# AS3364_DG412_bus_mixer_v1_4-4-layer.net
KiCad netlist of a schematic drawn in EAGLE
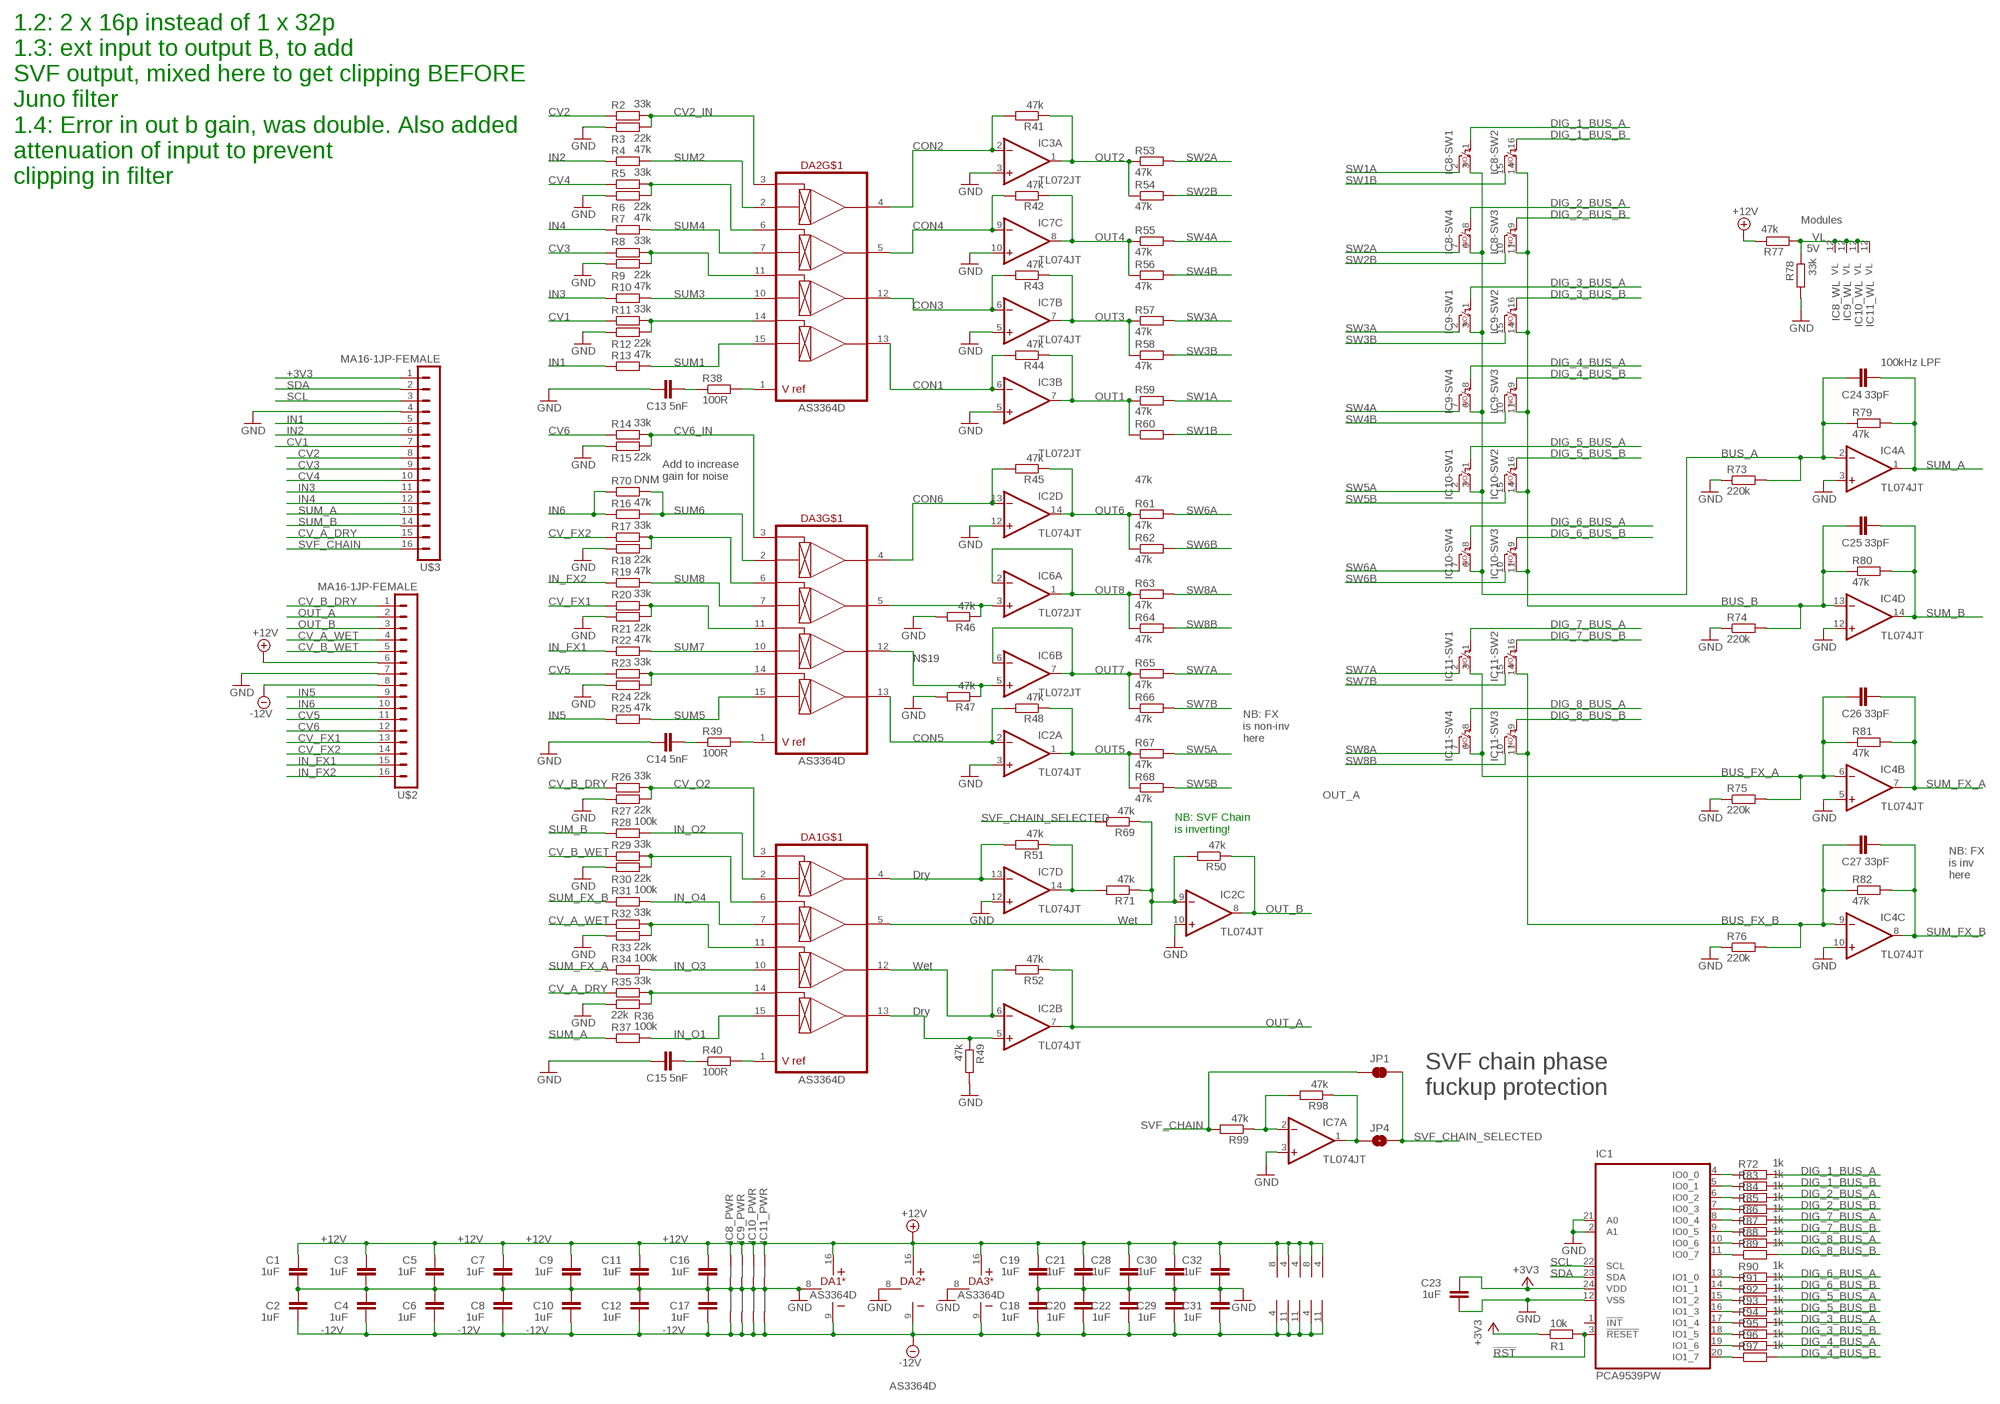
[diagram p0: schematic, sheet 1]

(export (version "E")
  (design (tool "Eeschema 10.0.6"))
  (components
    (comp (ref "C1")
      (value "1uF")
      (footprint "eagle-import:C0402-J")
      (libsource (lib "eagle-import") (part "C-EU-J0402"))
    )
    (comp (ref "C2")
      (value "1uF")
      (footprint "eagle-import:C0402-J")
      (libsource (lib "eagle-import") (part "C-EU-J0402"))
    )
    (comp (ref "C3")
      (value "1uF")
      (footprint "eagle-import:C0402-J")
      (libsource (lib "eagle-import") (part "C-EU-J0402"))
    )
    (comp (ref "C4")
      (value "1uF")
      (footprint "eagle-import:C0402-J")
      (libsource (lib "eagle-import") (part "C-EU-J0402"))
    )
    (comp (ref "C5")
      (value "1uF")
      (footprint "eagle-import:C0402-J")
      (libsource (lib "eagle-import") (part "C-EU-J0402"))
    )
    (comp (ref "C6")
      (value "1uF")
      (footprint "eagle-import:C0402-J")
      (libsource (lib "eagle-import") (part "C-EU-J0402"))
    )
    (comp (ref "C7")
      (value "1uF")
      (footprint "eagle-import:C0402-J")
      (libsource (lib "eagle-import") (part "C-EU-J0402"))
    )
    (comp (ref "C8")
      (value "1uF")
      (footprint "eagle-import:C0402-J")
      (libsource (lib "eagle-import") (part "C-EU-J0402"))
    )
    (comp (ref "C9")
      (value "1uF")
      (footprint "eagle-import:C0402-J")
      (libsource (lib "eagle-import") (part "C-EU-J0402"))
    )
    (comp (ref "C10")
      (value "1uF")
      (footprint "eagle-import:C0402-J")
      (libsource (lib "eagle-import") (part "C-EU-J0402"))
    )
    (comp (ref "C11")
      (value "1uF")
      (footprint "eagle-import:C0402-J")
      (libsource (lib "eagle-import") (part "C-EU-J0402"))
    )
    (comp (ref "C12")
      (value "1uF")
      (footprint "eagle-import:C0402-J")
      (libsource (lib "eagle-import") (part "C-EU-J0402"))
    )
    (comp (ref "C13")
      (value "5nF")
      (footprint "eagle-import:C0402-J")
      (libsource (lib "eagle-import") (part "C-EU-J0402"))
    )
    (comp (ref "C14")
      (value "5nF")
      (footprint "eagle-import:C0402-J")
      (libsource (lib "eagle-import") (part "C-EU-J0402"))
    )
    (comp (ref "C15")
      (value "5nF")
      (footprint "eagle-import:C0402-J")
      (libsource (lib "eagle-import") (part "C-EU-J0402"))
    )
    (comp (ref "C16")
      (value "1uF")
      (footprint "eagle-import:C0402-J")
      (libsource (lib "eagle-import") (part "C-EU-J0402"))
    )
    (comp (ref "C17")
      (value "1uF")
      (footprint "eagle-import:C0402-J")
      (libsource (lib "eagle-import") (part "C-EU-J0402"))
    )
    (comp (ref "C18")
      (value "1uF")
      (footprint "eagle-import:C0402-J")
      (libsource (lib "eagle-import") (part "C-EU-J0402"))
    )
    (comp (ref "C19")
      (value "1uF")
      (footprint "eagle-import:C0402-J")
      (libsource (lib "eagle-import") (part "C-EU-J0402"))
    )
    (comp (ref "C20")
      (value "1uF")
      (footprint "eagle-import:C0402-J")
      (libsource (lib "eagle-import") (part "C-EU-J0402"))
    )
    (comp (ref "C21")
      (value "1uF")
      (footprint "eagle-import:C0402-J")
      (libsource (lib "eagle-import") (part "C-EU-J0402"))
    )
    (comp (ref "C22")
      (value "1uF")
      (footprint "eagle-import:C0402-J")
      (libsource (lib "eagle-import") (part "C-EU-J0402"))
    )
    (comp (ref "C23")
      (value "1uF")
      (footprint "eagle-import:C0402-J")
      (libsource (lib "eagle-import") (part "C-EU-J0402"))
    )
    (comp (ref "C24")
      (value "33pF")
      (footprint "eagle-import:C0402-J")
      (libsource (lib "eagle-import") (part "C-EU-J0402"))
    )
    (comp (ref "C25")
      (value "33pF")
      (footprint "eagle-import:C0402-J")
      (libsource (lib "eagle-import") (part "C-EU-J0402"))
    )
    (comp (ref "C26")
      (value "33pF")
      (footprint "eagle-import:C0402-J")
      (libsource (lib "eagle-import") (part "C-EU-J0402"))
    )
    (comp (ref "C27")
      (value "33pF")
      (footprint "eagle-import:C0402-J")
      (libsource (lib "eagle-import") (part "C-EU-J0402"))
    )
    (comp (ref "C28")
      (value "1uF")
      (footprint "eagle-import:C0402-J")
      (libsource (lib "eagle-import") (part "C-EU-J0402"))
    )
    (comp (ref "C29")
      (value "1uF")
      (footprint "eagle-import:C0402-J")
      (libsource (lib "eagle-import") (part "C-EU-J0402"))
    )
    (comp (ref "C30")
      (value "1uF")
      (footprint "eagle-import:C0402-J")
      (libsource (lib "eagle-import") (part "C-EU-J0402"))
    )
    (comp (ref "C31")
      (value "1uF")
      (footprint "eagle-import:C0402-J")
      (libsource (lib "eagle-import") (part "C-EU-J0402"))
    )
    (comp (ref "C32")
      (value "1uF")
      (footprint "eagle-import:C0402-J")
      (libsource (lib "eagle-import") (part "C-EU-J0402"))
    )
    (comp (ref "DA1")
      (value "AS3364D")
      (footprint "eagle-import:DIL16J")
      (libsource (lib "eagle-import") (part "AS3364D"))
    )
    (comp (ref "DA2")
      (value "AS3364D")
      (footprint "eagle-import:DIL16J")
      (libsource (lib "eagle-import") (part "AS3364D"))
    )
    (comp (ref "DA3")
      (value "AS3364D")
      (footprint "eagle-import:DIL16J")
      (libsource (lib "eagle-import") (part "AS3364D"))
    )
    (comp (ref "IC1")
      (value "PCA9539PW")
      (footprint "eagle-import:TSSOP24J")
      (libsource (lib "eagle-import") (part "PCA9539PW"))
    )
    (comp (ref "IC2")
      (value "TL074JT")
      (footprint "eagle-import:TSSOP14J")
      (libsource (lib "eagle-import") (part "TL074JT"))
    )
    (comp (ref "IC3")
      (value "TL072JT")
      (footprint "eagle-import:TSSOP8J")
      (libsource (lib "eagle-import") (part "TL072JT"))
    )
    (comp (ref "IC4")
      (value "TL074JT")
      (footprint "eagle-import:TSSOP14J")
      (libsource (lib "eagle-import") (part "TL074JT"))
    )
    (comp (ref "IC6")
      (value "TL072JT")
      (footprint "eagle-import:TSSOP8J")
      (libsource (lib "eagle-import") (part "TL072JT"))
    )
    (comp (ref "IC7")
      (value "TL074JT")
      (footprint "eagle-import:TSSOP14J")
      (libsource (lib "eagle-import") (part "TL074JT"))
    )
    (comp (ref "IC8")
      (value "DG412-J")
      (footprint "eagle-import:DIL16J")
      (libsource (lib "eagle-import") (part "DG412-J"))
    )
    (comp (ref "IC9")
      (value "DG412-J")
      (footprint "eagle-import:DIL16J")
      (libsource (lib "eagle-import") (part "DG412-J"))
    )
    (comp (ref "IC10")
      (value "DG412-J")
      (footprint "eagle-import:DIL16J")
      (libsource (lib "eagle-import") (part "DG412-J"))
    )
    (comp (ref "IC11")
      (value "DG412-J")
      (footprint "eagle-import:DIL16J")
      (libsource (lib "eagle-import") (part "DG412-J"))
    )
    (comp (ref "JP1")
      (value "JUMPER-SMT_2_NC_TRACE_SILK-DNM")
      (footprint "eagle-import:SMT-JUMPER_2_NC_TRACE_SILK")
      (libsource (lib "eagle-import") (part "JUMPER-SMT_2_NC_TRACE_SILK"))
    )
    (comp (ref "JP4")
      (value "JUMPER-SMT_2_NO_SILK-DNM")
      (footprint "eagle-import:SMT-JUMPER_2_NO_SILK")
      (libsource (lib "eagle-import") (part "JUMPER-SMT_2_NO_SILK"))
    )
    (comp (ref "R1")
      (value "10k")
      (footprint "eagle-import:R0402")
      (libsource (lib "eagle-import") (part "R-EU_R0402"))
    )
    (comp (ref "R2")
      (value "33k")
      (footprint "eagle-import:R0402")
      (libsource (lib "eagle-import") (part "R-EU_R0402"))
    )
    (comp (ref "R3")
      (value "22k")
      (footprint "eagle-import:R0402")
      (libsource (lib "eagle-import") (part "R-EU_R0402"))
    )
    (comp (ref "R4")
      (value "47k")
      (footprint "eagle-import:R0402")
      (libsource (lib "eagle-import") (part "R-EU_R0402"))
    )
    (comp (ref "R5")
      (value "33k")
      (footprint "eagle-import:R0402")
      (libsource (lib "eagle-import") (part "R-EU_R0402"))
    )
    (comp (ref "R6")
      (value "22k")
      (footprint "eagle-import:R0402")
      (libsource (lib "eagle-import") (part "R-EU_R0402"))
    )
    (comp (ref "R7")
      (value "47k")
      (footprint "eagle-import:R0402")
      (libsource (lib "eagle-import") (part "R-EU_R0402"))
    )
    (comp (ref "R8")
      (value "33k")
      (footprint "eagle-import:R0402")
      (libsource (lib "eagle-import") (part "R-EU_R0402"))
    )
    (comp (ref "R9")
      (value "22k")
      (footprint "eagle-import:R0402")
      (libsource (lib "eagle-import") (part "R-EU_R0402"))
    )
    (comp (ref "R10")
      (value "47k")
      (footprint "eagle-import:R0402")
      (libsource (lib "eagle-import") (part "R-EU_R0402"))
    )
    (comp (ref "R11")
      (value "33k")
      (footprint "eagle-import:R0402")
      (libsource (lib "eagle-import") (part "R-EU_R0402"))
    )
    (comp (ref "R12")
      (value "22k")
      (footprint "eagle-import:R0402")
      (libsource (lib "eagle-import") (part "R-EU_R0402"))
    )
    (comp (ref "R13")
      (value "47k")
      (footprint "eagle-import:R0402")
      (libsource (lib "eagle-import") (part "R-EU_R0402"))
    )
    (comp (ref "R14")
      (value "33k")
      (footprint "eagle-import:R0402")
      (libsource (lib "eagle-import") (part "R-EU_R0402"))
    )
    (comp (ref "R15")
      (value "22k")
      (footprint "eagle-import:R0402")
      (libsource (lib "eagle-import") (part "R-EU_R0402"))
    )
    (comp (ref "R16")
      (value "47k")
      (footprint "eagle-import:R0402")
      (libsource (lib "eagle-import") (part "R-EU_R0402"))
    )
    (comp (ref "R17")
      (value "33k")
      (footprint "eagle-import:R0402")
      (libsource (lib "eagle-import") (part "R-EU_R0402"))
    )
    (comp (ref "R18")
      (value "22k")
      (footprint "eagle-import:R0402")
      (libsource (lib "eagle-import") (part "R-EU_R0402"))
    )
    (comp (ref "R19")
      (value "47k")
      (footprint "eagle-import:R0402")
      (libsource (lib "eagle-import") (part "R-EU_R0402"))
    )
    (comp (ref "R20")
      (value "33k")
      (footprint "eagle-import:R0402")
      (libsource (lib "eagle-import") (part "R-EU_R0402"))
    )
    (comp (ref "R21")
      (value "22k")
      (footprint "eagle-import:R0402")
      (libsource (lib "eagle-import") (part "R-EU_R0402"))
    )
    (comp (ref "R22")
      (value "47k")
      (footprint "eagle-import:R0402")
      (libsource (lib "eagle-import") (part "R-EU_R0402"))
    )
    (comp (ref "R23")
      (value "33k")
      (footprint "eagle-import:R0402")
      (libsource (lib "eagle-import") (part "R-EU_R0402"))
    )
    (comp (ref "R24")
      (value "22k")
      (footprint "eagle-import:R0402")
      (libsource (lib "eagle-import") (part "R-EU_R0402"))
    )
    (comp (ref "R25")
      (value "47k")
      (footprint "eagle-import:R0402")
      (libsource (lib "eagle-import") (part "R-EU_R0402"))
    )
    (comp (ref "R26")
      (value "33k")
      (footprint "eagle-import:R0402")
      (libsource (lib "eagle-import") (part "R-EU_R0402"))
    )
    (comp (ref "R27")
      (value "22k")
      (footprint "eagle-import:R0402")
      (libsource (lib "eagle-import") (part "R-EU_R0402"))
    )
    (comp (ref "R28")
      (value "100k")
      (footprint "eagle-import:R0402")
      (libsource (lib "eagle-import") (part "R-EU_R0402"))
    )
    (comp (ref "R29")
      (value "33k")
      (footprint "eagle-import:R0402")
      (libsource (lib "eagle-import") (part "R-EU_R0402"))
    )
    (comp (ref "R30")
      (value "22k")
      (footprint "eagle-import:R0402")
      (libsource (lib "eagle-import") (part "R-EU_R0402"))
    )
    (comp (ref "R31")
      (value "100k")
      (footprint "eagle-import:R0402")
      (libsource (lib "eagle-import") (part "R-EU_R0402"))
    )
    (comp (ref "R32")
      (value "33k")
      (footprint "eagle-import:R0402")
      (libsource (lib "eagle-import") (part "R-EU_R0402"))
    )
    (comp (ref "R33")
      (value "22k")
      (footprint "eagle-import:R0402")
      (libsource (lib "eagle-import") (part "R-EU_R0402"))
    )
    (comp (ref "R34")
      (value "100k")
      (footprint "eagle-import:R0402")
      (libsource (lib "eagle-import") (part "R-EU_R0402"))
    )
    (comp (ref "R35")
      (value "33k")
      (footprint "eagle-import:R0402")
      (libsource (lib "eagle-import") (part "R-EU_R0402"))
    )
    (comp (ref "R36")
      (value "22k")
      (footprint "eagle-import:R0402")
      (libsource (lib "eagle-import") (part "R-EU_R0402"))
    )
    (comp (ref "R37")
      (value "100k")
      (footprint "eagle-import:R0402")
      (libsource (lib "eagle-import") (part "R-EU_R0402"))
    )
    (comp (ref "R38")
      (value "100R")
      (footprint "eagle-import:R0402")
      (libsource (lib "eagle-import") (part "R-EU_R0402"))
    )
    (comp (ref "R39")
      (value "100R")
      (footprint "eagle-import:R0402")
      (libsource (lib "eagle-import") (part "R-EU_R0402"))
    )
    (comp (ref "R40")
      (value "100R")
      (footprint "eagle-import:R0402")
      (libsource (lib "eagle-import") (part "R-EU_R0402"))
    )
    (comp (ref "R41")
      (value "47k")
      (footprint "eagle-import:R0402")
      (libsource (lib "eagle-import") (part "R-EU_R0402"))
    )
    (comp (ref "R42")
      (value "47k")
      (footprint "eagle-import:R0402")
      (libsource (lib "eagle-import") (part "R-EU_R0402"))
    )
    (comp (ref "R43")
      (value "47k")
      (footprint "eagle-import:R0402")
      (libsource (lib "eagle-import") (part "R-EU_R0402"))
    )
    (comp (ref "R44")
      (value "47k")
      (footprint "eagle-import:R0402")
      (libsource (lib "eagle-import") (part "R-EU_R0402"))
    )
    (comp (ref "R45")
      (value "47k")
      (footprint "eagle-import:R0402")
      (libsource (lib "eagle-import") (part "R-EU_R0402"))
    )
    (comp (ref "R46")
      (value "47k")
      (footprint "eagle-import:R0402")
      (libsource (lib "eagle-import") (part "R-EU_R0402"))
    )
    (comp (ref "R47")
      (value "47k")
      (footprint "eagle-import:R0402")
      (libsource (lib "eagle-import") (part "R-EU_R0402"))
    )
    (comp (ref "R48")
      (value "47k")
      (footprint "eagle-import:R0402")
      (libsource (lib "eagle-import") (part "R-EU_R0402"))
    )
    (comp (ref "R49")
      (value "47k")
      (footprint "eagle-import:R0402")
      (libsource (lib "eagle-import") (part "R-EU_R0402"))
    )
    (comp (ref "R50")
      (value "47k")
      (footprint "eagle-import:R0402")
      (libsource (lib "eagle-import") (part "R-EU_R0402"))
    )
    (comp (ref "R51")
      (value "47k")
      (footprint "eagle-import:R0402")
      (libsource (lib "eagle-import") (part "R-EU_R0402"))
    )
    (comp (ref "R52")
      (value "47k")
      (footprint "eagle-import:R0402")
      (libsource (lib "eagle-import") (part "R-EU_R0402"))
    )
    (comp (ref "R53")
      (value "47k")
      (footprint "eagle-import:R0402")
      (libsource (lib "eagle-import") (part "R-EU_R0402"))
    )
    (comp (ref "R54")
      (value "47k")
      (footprint "eagle-import:R0402")
      (libsource (lib "eagle-import") (part "R-EU_R0402"))
    )
    (comp (ref "R55")
      (value "47k")
      (footprint "eagle-import:R0402")
      (libsource (lib "eagle-import") (part "R-EU_R0402"))
    )
    (comp (ref "R56")
      (value "47k")
      (footprint "eagle-import:R0402")
      (libsource (lib "eagle-import") (part "R-EU_R0402"))
    )
    (comp (ref "R57")
      (value "47k")
      (footprint "eagle-import:R0402")
      (libsource (lib "eagle-import") (part "R-EU_R0402"))
    )
    (comp (ref "R58")
      (value "47k")
      (footprint "eagle-import:R0402")
      (libsource (lib "eagle-import") (part "R-EU_R0402"))
    )
    (comp (ref "R59")
      (value "47k")
      (footprint "eagle-import:R0402")
      (libsource (lib "eagle-import") (part "R-EU_R0402"))
    )
    (comp (ref "R60")
      (value "47k")
      (footprint "eagle-import:R0402")
      (libsource (lib "eagle-import") (part "R-EU_R0402"))
    )
    (comp (ref "R61")
      (value "47k")
      (footprint "eagle-import:R0402")
      (libsource (lib "eagle-import") (part "R-EU_R0402"))
    )
    (comp (ref "R62")
      (value "47k")
      (footprint "eagle-import:R0402")
      (libsource (lib "eagle-import") (part "R-EU_R0402"))
    )
    (comp (ref "R63")
      (value "47k")
      (footprint "eagle-import:R0402")
      (libsource (lib "eagle-import") (part "R-EU_R0402"))
    )
    (comp (ref "R64")
      (value "47k")
      (footprint "eagle-import:R0402")
      (libsource (lib "eagle-import") (part "R-EU_R0402"))
    )
    (comp (ref "R65")
      (value "47k")
      (footprint "eagle-import:R0402")
      (libsource (lib "eagle-import") (part "R-EU_R0402"))
    )
    (comp (ref "R66")
      (value "47k")
      (footprint "eagle-import:R0402")
      (libsource (lib "eagle-import") (part "R-EU_R0402"))
    )
    (comp (ref "R67")
      (value "47k")
      (footprint "eagle-import:R0402")
      (libsource (lib "eagle-import") (part "R-EU_R0402"))
    )
    (comp (ref "R68")
      (value "47k")
      (footprint "eagle-import:R0402")
      (libsource (lib "eagle-import") (part "R-EU_R0402"))
    )
    (comp (ref "R69")
      (value "47k")
      (footprint "eagle-import:R0402")
      (libsource (lib "eagle-import") (part "R-EU_R0402"))
    )
    (comp (ref "R70")
      (value "DNM")
      (footprint "eagle-import:R0805")
      (libsource (lib "eagle-import") (part "R-EU_R0805"))
    )
    (comp (ref "R71")
      (value "47k")
      (footprint "eagle-import:R0402")
      (libsource (lib "eagle-import") (part "R-EU_R0402"))
    )
    (comp (ref "R72")
      (value "1k")
      (footprint "eagle-import:R0402")
      (libsource (lib "eagle-import") (part "R-EU_R0402"))
    )
    (comp (ref "R73")
      (value "220k")
      (footprint "eagle-import:R0603")
      (libsource (lib "eagle-import") (part "R-EU_R0603"))
    )
    (comp (ref "R74")
      (value "220k")
      (footprint "eagle-import:R0603")
      (libsource (lib "eagle-import") (part "R-EU_R0603"))
    )
    (comp (ref "R75")
      (value "220k")
      (footprint "eagle-import:R0603")
      (libsource (lib "eagle-import") (part "R-EU_R0603"))
    )
    (comp (ref "R76")
      (value "220k")
      (footprint "eagle-import:R0603")
      (libsource (lib "eagle-import") (part "R-EU_R0603"))
    )
    (comp (ref "R77")
      (value "47k")
      (footprint "eagle-import:R0402")
      (libsource (lib "eagle-import") (part "R-EU_R0402"))
    )
    (comp (ref "R78")
      (value "33k")
      (footprint "eagle-import:R0402")
      (libsource (lib "eagle-import") (part "R-EU_R0402"))
    )
    (comp (ref "R79")
      (value "47k")
      (footprint "eagle-import:R0402")
      (libsource (lib "eagle-import") (part "R-EU_R0402"))
    )
    (comp (ref "R80")
      (value "47k")
      (footprint "eagle-import:R0402")
      (libsource (lib "eagle-import") (part "R-EU_R0402"))
    )
    (comp (ref "R81")
      (value "47k")
      (footprint "eagle-import:R0402")
      (libsource (lib "eagle-import") (part "R-EU_R0402"))
    )
    (comp (ref "R82")
      (value "47k")
      (footprint "eagle-import:R0402")
      (libsource (lib "eagle-import") (part "R-EU_R0402"))
    )
    (comp (ref "R83")
      (value "1k")
      (footprint "eagle-import:R0402")
      (libsource (lib "eagle-import") (part "R-EU_R0402"))
    )
    (comp (ref "R84")
      (value "1k")
      (footprint "eagle-import:R0402")
      (libsource (lib "eagle-import") (part "R-EU_R0402"))
    )
    (comp (ref "R85")
      (value "1k")
      (footprint "eagle-import:R0402")
      (libsource (lib "eagle-import") (part "R-EU_R0402"))
    )
    (comp (ref "R86")
      (value "1k")
      (footprint "eagle-import:R0402")
      (libsource (lib "eagle-import") (part "R-EU_R0402"))
    )
    (comp (ref "R87")
      (value "1k")
      (footprint "eagle-import:R0402")
      (libsource (lib "eagle-import") (part "R-EU_R0402"))
    )
    (comp (ref "R88")
      (value "1k")
      (footprint "eagle-import:R0402")
      (libsource (lib "eagle-import") (part "R-EU_R0402"))
    )
    (comp (ref "R89")
      (value "1k")
      (footprint "eagle-import:R0402")
      (libsource (lib "eagle-import") (part "R-EU_R0402"))
    )
    (comp (ref "R90")
      (value "1k")
      (footprint "eagle-import:R0402")
      (libsource (lib "eagle-import") (part "R-EU_R0402"))
    )
    (comp (ref "R91")
      (value "1k")
      (footprint "eagle-import:R0402")
      (libsource (lib "eagle-import") (part "R-EU_R0402"))
    )
    (comp (ref "R92")
      (value "1k")
      (footprint "eagle-import:R0402")
      (libsource (lib "eagle-import") (part "R-EU_R0402"))
    )
    (comp (ref "R93")
      (value "1k")
      (footprint "eagle-import:R0402")
      (libsource (lib "eagle-import") (part "R-EU_R0402"))
    )
    (comp (ref "R94")
      (value "1k")
      (footprint "eagle-import:R0402")
      (libsource (lib "eagle-import") (part "R-EU_R0402"))
    )
    (comp (ref "R95")
      (value "1k")
      (footprint "eagle-import:R0402")
      (libsource (lib "eagle-import") (part "R-EU_R0402"))
    )
    (comp (ref "R96")
      (value "1k")
      (footprint "eagle-import:R0402")
      (libsource (lib "eagle-import") (part "R-EU_R0402"))
    )
    (comp (ref "R97")
      (value "1k")
      (footprint "eagle-import:R0402")
      (libsource (lib "eagle-import") (part "R-EU_R0402"))
    )
    (comp (ref "R98")
      (value "47k")
      (footprint "eagle-import:R0402")
      (libsource (lib "eagle-import") (part "R-EU_R0402"))
    )
    (comp (ref "R99")
      (value "47k")
      (footprint "eagle-import:R0402")
      (libsource (lib "eagle-import") (part "R-EU_R0402"))
    )
    (comp (ref "U$2")
      (value "MA16-1JP-FEMALE")
      (footprint "eagle-import:SIP-PIN16-1J")
      (libsource (lib "eagle-import") (part "MA16-1JP"))
    )
    (comp (ref "U$3")
      (value "MA16-1JP-FEMALE")
      (footprint "eagle-import:SIP-PIN16-1J")
      (libsource (lib "eagle-import") (part "MA16-1JP"))
    )
  )
  (nets
    (net (code "1") (name "+3V3") (class "Default")
      (node (ref "C23") (pin "2") (pinfunction "2_2") (pintype "passive"))
      (node (ref "IC1") (pin "24") (pinfunction "VDD_24") (pintype "power_in"))
      (node (ref "R1") (pin "1") (pinfunction "1_1") (pintype "passive"))
      (node (ref "U$3") (pin "1") (pinfunction "1_1") (pintype "passive"))
    )
    (net (code "2") (name "+12V") (class "Default")
      (node (ref "C1") (pin "2") (pinfunction "2_2") (pintype "passive"))
      (node (ref "C11") (pin "2") (pinfunction "2_2") (pintype "passive"))
      (node (ref "C16") (pin "2") (pinfunction "2_2") (pintype "passive"))
      (node (ref "C19") (pin "2") (pinfunction "2_2") (pintype "passive"))
      (node (ref "C21") (pin "2") (pinfunction "2_2") (pintype "passive"))
      (node (ref "C28") (pin "2") (pinfunction "2_2") (pintype "passive"))
      (node (ref "C3") (pin "2") (pinfunction "2_2") (pintype "passive"))
      (node (ref "C30") (pin "2") (pinfunction "2_2") (pintype "passive"))
      (node (ref "C32") (pin "2") (pinfunction "2_2") (pintype "passive"))
      (node (ref "C5") (pin "2") (pinfunction "2_2") (pintype "passive"))
      (node (ref "C7") (pin "2") (pinfunction "2_2") (pintype "passive"))
      (node (ref "C9") (pin "2") (pinfunction "2_2") (pintype "passive"))
      (node (ref "DA1") (pin "16") (pinfunction "V+_16") (pintype "power_in"))
      (node (ref "DA2") (pin "16") (pinfunction "V+_16") (pintype "power_in"))
      (node (ref "DA3") (pin "16") (pinfunction "V+_16") (pintype "power_in"))
      (node (ref "IC10") (pin "13") (pinfunction "+15V_13") (pintype "power_in"))
      (node (ref "IC11") (pin "13") (pinfunction "+15V_13") (pintype "power_in"))
      (node (ref "IC2") (pin "4") (pinfunction "V+_4") (pintype "power_in"))
      (node (ref "IC3") (pin "8") (pinfunction "V+_8") (pintype "power_in"))
      (node (ref "IC4") (pin "4") (pinfunction "V+_4") (pintype "power_in"))
      (node (ref "IC6") (pin "8") (pinfunction "V+_8") (pintype "power_in"))
      (node (ref "IC7") (pin "4") (pinfunction "V+_4") (pintype "power_in"))
      (node (ref "IC8") (pin "13") (pinfunction "+15V_13") (pintype "power_in"))
      (node (ref "IC9") (pin "13") (pinfunction "+15V_13") (pintype "power_in"))
      (node (ref "R77") (pin "1") (pinfunction "1_1") (pintype "passive"))
      (node (ref "U$2") (pin "6") (pinfunction "6_6") (pintype "passive"))
    )
    (net (code "3") (name "-12V") (class "Default")
      (node (ref "C10") (pin "1") (pinfunction "1_1") (pintype "passive"))
      (node (ref "C12") (pin "1") (pinfunction "1_1") (pintype "passive"))
      (node (ref "C17") (pin "1") (pinfunction "1_1") (pintype "passive"))
      (node (ref "C18") (pin "1") (pinfunction "1_1") (pintype "passive"))
      (node (ref "C2") (pin "1") (pinfunction "1_1") (pintype "passive"))
      (node (ref "C20") (pin "1") (pinfunction "1_1") (pintype "passive"))
      (node (ref "C22") (pin "1") (pinfunction "1_1") (pintype "passive"))
      (node (ref "C29") (pin "1") (pinfunction "1_1") (pintype "passive"))
      (node (ref "C31") (pin "1") (pinfunction "1_1") (pintype "passive"))
      (node (ref "C4") (pin "1") (pinfunction "1_1") (pintype "passive"))
      (node (ref "C6") (pin "1") (pinfunction "1_1") (pintype "passive"))
      (node (ref "C8") (pin "1") (pinfunction "1_1") (pintype "passive"))
      (node (ref "DA1") (pin "9") (pinfunction "V-_9") (pintype "power_in"))
      (node (ref "DA2") (pin "9") (pinfunction "V-_9") (pintype "power_in"))
      (node (ref "DA3") (pin "9") (pinfunction "V-_9") (pintype "power_in"))
      (node (ref "IC10") (pin "4") (pinfunction "-15V_4") (pintype "power_in"))
      (node (ref "IC11") (pin "4") (pinfunction "-15V_4") (pintype "power_in"))
      (node (ref "IC2") (pin "11") (pinfunction "V-_11") (pintype "power_in"))
      (node (ref "IC3") (pin "4") (pinfunction "V-_4") (pintype "power_in"))
      (node (ref "IC4") (pin "11") (pinfunction "V-_11") (pintype "power_in"))
      (node (ref "IC6") (pin "4") (pinfunction "V-_4") (pintype "power_in"))
      (node (ref "IC7") (pin "11") (pinfunction "V-_11") (pintype "power_in"))
      (node (ref "IC8") (pin "4") (pinfunction "-15V_4") (pintype "power_in"))
      (node (ref "IC9") (pin "4") (pinfunction "-15V_4") (pintype "power_in"))
      (node (ref "U$2") (pin "8") (pinfunction "8_8") (pintype "passive"))
    )
    (net (code "4") (name "/BUS_A") (class "Default")
      (node (ref "C24") (pin "1") (pinfunction "1_1") (pintype "passive"))
      (node (ref "IC10") (pin "3") (pinfunction "S_3") (pintype "bidirectional"))
      (node (ref "IC10") (pin "6") (pinfunction "S_6") (pintype "bidirectional"))
      (node (ref "IC4") (pin "2") (pinfunction "-IN_2") (pintype "input"))
      (node (ref "IC8") (pin "3") (pinfunction "S_3") (pintype "bidirectional"))
      (node (ref "IC8") (pin "6") (pinfunction "S_6") (pintype "bidirectional"))
      (node (ref "IC9") (pin "3") (pinfunction "S_3") (pintype "bidirectional"))
      (node (ref "IC9") (pin "6") (pinfunction "S_6") (pintype "bidirectional"))
      (node (ref "R73") (pin "2") (pinfunction "2_2") (pintype "passive"))
      (node (ref "R79") (pin "1") (pinfunction "1_1") (pintype "passive"))
    )
    (net (code "5") (name "/BUS_B") (class "Default")
      (node (ref "C25") (pin "1") (pinfunction "1_1") (pintype "passive"))
      (node (ref "IC10") (pin "11") (pinfunction "S_11") (pintype "bidirectional"))
      (node (ref "IC10") (pin "14") (pinfunction "S_14") (pintype "bidirectional"))
      (node (ref "IC4") (pin "13") (pinfunction "-IN_13") (pintype "input"))
      (node (ref "IC8") (pin "11") (pinfunction "S_11") (pintype "bidirectional"))
      (node (ref "IC8") (pin "14") (pinfunction "S_14") (pintype "bidirectional"))
      (node (ref "IC9") (pin "11") (pinfunction "S_11") (pintype "bidirectional"))
      (node (ref "IC9") (pin "14") (pinfunction "S_14") (pintype "bidirectional"))
      (node (ref "R74") (pin "2") (pinfunction "2_2") (pintype "passive"))
      (node (ref "R80") (pin "1") (pinfunction "1_1") (pintype "passive"))
    )
    (net (code "6") (name "/BUS_FX_A") (class "Default")
      (node (ref "C26") (pin "1") (pinfunction "1_1") (pintype "passive"))
      (node (ref "IC11") (pin "3") (pinfunction "S_3") (pintype "bidirectional"))
      (node (ref "IC11") (pin "6") (pinfunction "S_6") (pintype "bidirectional"))
      (node (ref "IC4") (pin "6") (pinfunction "-IN_6") (pintype "input"))
      (node (ref "R75") (pin "2") (pinfunction "2_2") (pintype "passive"))
      (node (ref "R81") (pin "1") (pinfunction "1_1") (pintype "passive"))
    )
    (net (code "7") (name "/BUS_FX_B") (class "Default")
      (node (ref "C27") (pin "1") (pinfunction "1_1") (pintype "passive"))
      (node (ref "IC11") (pin "11") (pinfunction "S_11") (pintype "bidirectional"))
      (node (ref "IC11") (pin "14") (pinfunction "S_14") (pintype "bidirectional"))
      (node (ref "IC4") (pin "9") (pinfunction "-IN_9") (pintype "input"))
      (node (ref "R76") (pin "2") (pinfunction "2_2") (pintype "passive"))
      (node (ref "R82") (pin "1") (pinfunction "1_1") (pintype "passive"))
    )
    (net (code "8") (name "/CON1") (class "Default")
      (node (ref "DA2") (pin "13") (pinfunction "OUT4_13") (pintype "output"))
      (node (ref "IC3") (pin "6") (pinfunction "-IN_6") (pintype "input"))
      (node (ref "R44") (pin "2") (pinfunction "2_2") (pintype "passive"))
    )
    (net (code "9") (name "/CON2") (class "Default")
      (node (ref "DA2") (pin "4") (pinfunction "OUT1_4") (pintype "output"))
      (node (ref "IC3") (pin "2") (pinfunction "-IN_2") (pintype "input"))
      (node (ref "R41") (pin "2") (pinfunction "2_2") (pintype "passive"))
    )
    (net (code "10") (name "/CON3") (class "Default")
      (node (ref "DA2") (pin "12") (pinfunction "OUT3_12") (pintype "output"))
      (node (ref "IC7") (pin "6") (pinfunction "-IN_6") (pintype "input"))
      (node (ref "R43") (pin "2") (pinfunction "2_2") (pintype "passive"))
    )
    (net (code "11") (name "/CON4") (class "Default")
      (node (ref "DA2") (pin "5") (pinfunction "OUT2_5") (pintype "output"))
      (node (ref "IC7") (pin "9") (pinfunction "-IN_9") (pintype "input"))
      (node (ref "R42") (pin "2") (pinfunction "2_2") (pintype "passive"))
    )
    (net (code "12") (name "/CON5") (class "Default")
      (node (ref "DA3") (pin "13") (pinfunction "OUT4_13") (pintype "output"))
      (node (ref "IC2") (pin "2") (pinfunction "-IN_2") (pintype "input"))
      (node (ref "R48") (pin "2") (pinfunction "2_2") (pintype "passive"))
    )
    (net (code "13") (name "/CON6") (class "Default")
      (node (ref "DA3") (pin "4") (pinfunction "OUT1_4") (pintype "output"))
      (node (ref "IC2") (pin "13") (pinfunction "-IN_13") (pintype "input"))
      (node (ref "R45") (pin "2") (pinfunction "2_2") (pintype "passive"))
    )
    (net (code "14") (name "/CV1") (class "Default")
      (node (ref "R11") (pin "1") (pinfunction "1_1") (pintype "passive"))
      (node (ref "U$3") (pin "7") (pinfunction "7_7") (pintype "passive"))
    )
    (net (code "15") (name "/CV2") (class "Default")
      (node (ref "R2") (pin "1") (pinfunction "1_1") (pintype "passive"))
      (node (ref "U$3") (pin "8") (pinfunction "8_8") (pintype "passive"))
    )
    (net (code "16") (name "/CV2_IN") (class "Default")
      (node (ref "DA2") (pin "3") (pinfunction "CV1_3") (pintype "input"))
      (node (ref "R2") (pin "2") (pinfunction "2_2") (pintype "passive"))
      (node (ref "R3") (pin "2") (pinfunction "2_2") (pintype "passive"))
    )
    (net (code "17") (name "/CV3") (class "Default")
      (node (ref "R8") (pin "1") (pinfunction "1_1") (pintype "passive"))
      (node (ref "U$3") (pin "9") (pinfunction "9_9") (pintype "passive"))
    )
    (net (code "18") (name "/CV4") (class "Default")
      (node (ref "R5") (pin "1") (pinfunction "1_1") (pintype "passive"))
      (node (ref "U$3") (pin "10") (pinfunction "10_10") (pintype "passive"))
    )
    (net (code "19") (name "/CV5") (class "Default")
      (node (ref "R23") (pin "1") (pinfunction "1_1") (pintype "passive"))
      (node (ref "U$2") (pin "11") (pinfunction "11_11") (pintype "passive"))
    )
    (net (code "20") (name "/CV6") (class "Default")
      (node (ref "R14") (pin "1") (pinfunction "1_1") (pintype "passive"))
      (node (ref "U$2") (pin "12") (pinfunction "12_12") (pintype "passive"))
    )
    (net (code "21") (name "/CV6_IN") (class "Default")
      (node (ref "DA3") (pin "3") (pinfunction "CV1_3") (pintype "input"))
      (node (ref "R14") (pin "2") (pinfunction "2_2") (pintype "passive"))
      (node (ref "R15") (pin "2") (pinfunction "2_2") (pintype "passive"))
    )
    (net (code "22") (name "/CV_A_DRY") (class "Default")
      (node (ref "R35") (pin "1") (pinfunction "1_1") (pintype "passive"))
      (node (ref "U$3") (pin "15") (pinfunction "15_15") (pintype "passive"))
    )
    (net (code "23") (name "/CV_A_WET") (class "Default")
      (node (ref "R32") (pin "1") (pinfunction "1_1") (pintype "passive"))
      (node (ref "U$2") (pin "4") (pinfunction "4_4") (pintype "passive"))
    )
    (net (code "24") (name "/CV_B_DRY") (class "Default")
      (node (ref "R26") (pin "1") (pinfunction "1_1") (pintype "passive"))
      (node (ref "U$2") (pin "1") (pinfunction "1_1") (pintype "passive"))
    )
    (net (code "25") (name "/CV_B_WET") (class "Default")
      (node (ref "R29") (pin "1") (pinfunction "1_1") (pintype "passive"))
      (node (ref "U$2") (pin "5") (pinfunction "5_5") (pintype "passive"))
    )
    (net (code "26") (name "/CV_FX1") (class "Default")
      (node (ref "R20") (pin "1") (pinfunction "1_1") (pintype "passive"))
      (node (ref "U$2") (pin "13") (pinfunction "13_13") (pintype "passive"))
    )
    (net (code "27") (name "/CV_FX2") (class "Default")
      (node (ref "R17") (pin "1") (pinfunction "1_1") (pintype "passive"))
      (node (ref "U$2") (pin "14") (pinfunction "14_14") (pintype "passive"))
    )
    (net (code "28") (name "/CV_O2") (class "Default")
      (node (ref "DA1") (pin "3") (pinfunction "CV1_3") (pintype "input"))
      (node (ref "R26") (pin "2") (pinfunction "2_2") (pintype "passive"))
      (node (ref "R27") (pin "2") (pinfunction "2_2") (pintype "passive"))
    )
    (net (code "29") (name "/DIG_1_BUS_A") (class "Default")
      (node (ref "IC8") (pin "1") (pinfunction "C_1") (pintype "bidirectional"))
      (node (ref "R72") (pin "2") (pinfunction "2_2") (pintype "passive"))
    )
    (net (code "30") (name "/DIG_1_BUS_B") (class "Default")
      (node (ref "IC8") (pin "16") (pinfunction "C_16") (pintype "bidirectional"))
      (node (ref "R83") (pin "2") (pinfunction "2_2") (pintype "passive"))
    )
    (net (code "31") (name "/DIG_2_BUS_A") (class "Default")
      (node (ref "IC8") (pin "8") (pinfunction "C_8") (pintype "bidirectional"))
      (node (ref "R84") (pin "2") (pinfunction "2_2") (pintype "passive"))
    )
    (net (code "32") (name "/DIG_2_BUS_B") (class "Default")
      (node (ref "IC8") (pin "9") (pinfunction "C_9") (pintype "bidirectional"))
      (node (ref "R85") (pin "2") (pinfunction "2_2") (pintype "passive"))
    )
    (net (code "33") (name "/DIG_3_BUS_A") (class "Default")
      (node (ref "IC9") (pin "1") (pinfunction "C_1") (pintype "bidirectional"))
      (node (ref "R94") (pin "2") (pinfunction "2_2") (pintype "passive"))
    )
    (net (code "34") (name "/DIG_3_BUS_B") (class "Default")
      (node (ref "IC9") (pin "16") (pinfunction "C_16") (pintype "bidirectional"))
      (node (ref "R95") (pin "2") (pinfunction "2_2") (pintype "passive"))
    )
    (net (code "35") (name "/DIG_4_BUS_A") (class "Default")
      (node (ref "IC9") (pin "8") (pinfunction "C_8") (pintype "bidirectional"))
      (node (ref "R96") (pin "2") (pinfunction "2_2") (pintype "passive"))
    )
    (net (code "36") (name "/DIG_4_BUS_B") (class "Default")
      (node (ref "IC9") (pin "9") (pinfunction "C_9") (pintype "bidirectional"))
      (node (ref "R97") (pin "2") (pinfunction "2_2") (pintype "passive"))
    )
    (net (code "37") (name "/DIG_5_BUS_A") (class "Default")
      (node (ref "IC10") (pin "1") (pinfunction "C_1") (pintype "bidirectional"))
      (node (ref "R92") (pin "2") (pinfunction "2_2") (pintype "passive"))
    )
    (net (code "38") (name "/DIG_5_BUS_B") (class "Default")
      (node (ref "IC10") (pin "16") (pinfunction "C_16") (pintype "bidirectional"))
      (node (ref "R93") (pin "2") (pinfunction "2_2") (pintype "passive"))
    )
    (net (code "39") (name "/DIG_6_BUS_A") (class "Default")
      (node (ref "IC10") (pin "8") (pinfunction "C_8") (pintype "bidirectional"))
      (node (ref "R90") (pin "2") (pinfunction "2_2") (pintype "passive"))
    )
    (net (code "40") (name "/DIG_6_BUS_B") (class "Default")
      (node (ref "IC10") (pin "9") (pinfunction "C_9") (pintype "bidirectional"))
      (node (ref "R91") (pin "2") (pinfunction "2_2") (pintype "passive"))
    )
    (net (code "41") (name "/DIG_7_BUS_A") (class "Default")
      (node (ref "IC11") (pin "1") (pinfunction "C_1") (pintype "bidirectional"))
      (node (ref "R86") (pin "2") (pinfunction "2_2") (pintype "passive"))
    )
    (net (code "42") (name "/DIG_7_BUS_B") (class "Default")
      (node (ref "IC11") (pin "16") (pinfunction "C_16") (pintype "bidirectional"))
      (node (ref "R87") (pin "2") (pinfunction "2_2") (pintype "passive"))
    )
    (net (code "43") (name "/DIG_8_BUS_A") (class "Default")
      (node (ref "IC11") (pin "8") (pinfunction "C_8") (pintype "bidirectional"))
      (node (ref "R88") (pin "2") (pinfunction "2_2") (pintype "passive"))
    )
    (net (code "44") (name "/DIG_8_BUS_B") (class "Default")
      (node (ref "IC11") (pin "9") (pinfunction "C_9") (pintype "bidirectional"))
      (node (ref "R89") (pin "2") (pinfunction "2_2") (pintype "passive"))
    )
    (net (code "45") (name "/IN1") (class "Default")
      (node (ref "R13") (pin "1") (pinfunction "1_1") (pintype "passive"))
      (node (ref "U$3") (pin "5") (pinfunction "5_5") (pintype "passive"))
    )
    (net (code "46") (name "/IN2") (class "Default")
      (node (ref "R4") (pin "1") (pinfunction "1_1") (pintype "passive"))
      (node (ref "U$3") (pin "6") (pinfunction "6_6") (pintype "passive"))
    )
    (net (code "47") (name "/IN3") (class "Default")
      (node (ref "R10") (pin "1") (pinfunction "1_1") (pintype "passive"))
      (node (ref "U$3") (pin "11") (pinfunction "11_11") (pintype "passive"))
    )
    (net (code "48") (name "/IN4") (class "Default")
      (node (ref "R7") (pin "1") (pinfunction "1_1") (pintype "passive"))
      (node (ref "U$3") (pin "12") (pinfunction "12_12") (pintype "passive"))
    )
    (net (code "49") (name "/IN5") (class "Default")
      (node (ref "R25") (pin "1") (pinfunction "1_1") (pintype "passive"))
      (node (ref "U$2") (pin "9") (pinfunction "9_9") (pintype "passive"))
    )
    (net (code "50") (name "/IN6") (class "Default")
      (node (ref "R16") (pin "1") (pinfunction "1_1") (pintype "passive"))
      (node (ref "R70") (pin "1") (pinfunction "1_1") (pintype "passive"))
      (node (ref "U$2") (pin "10") (pinfunction "10_10") (pintype "passive"))
    )
    (net (code "51") (name "/IN_FX1") (class "Default")
      (node (ref "R22") (pin "1") (pinfunction "1_1") (pintype "passive"))
      (node (ref "U$2") (pin "15") (pinfunction "15_15") (pintype "passive"))
    )
    (net (code "52") (name "/IN_FX2") (class "Default")
      (node (ref "R19") (pin "1") (pinfunction "1_1") (pintype "passive"))
      (node (ref "U$2") (pin "16") (pinfunction "16_16") (pintype "passive"))
    )
    (net (code "53") (name "/IN_O1") (class "Default")
      (node (ref "DA1") (pin "15") (pinfunction "IN4_15") (pintype "input"))
      (node (ref "R37") (pin "2") (pinfunction "2_2") (pintype "passive"))
    )
    (net (code "54") (name "/IN_O2") (class "Default")
      (node (ref "DA1") (pin "2") (pinfunction "IN1_2") (pintype "input"))
      (node (ref "R28") (pin "2") (pinfunction "2_2") (pintype "passive"))
    )
    (net (code "55") (name "/IN_O3") (class "Default")
      (node (ref "DA1") (pin "10") (pinfunction "IN3_10") (pintype "input"))
      (node (ref "R34") (pin "2") (pinfunction "2_2") (pintype "passive"))
    )
    (net (code "56") (name "/IN_O4") (class "Default")
      (node (ref "DA1") (pin "7") (pinfunction "IN2_7") (pintype "input"))
      (node (ref "R31") (pin "2") (pinfunction "2_2") (pintype "passive"))
    )
    (net (code "57") (name "/N$19") (class "Default")
      (node (ref "DA3") (pin "12") (pinfunction "OUT3_12") (pintype "output"))
      (node (ref "IC6") (pin "5") (pinfunction "+IN_5") (pintype "input"))
      (node (ref "R47") (pin "1") (pinfunction "1_1") (pintype "passive"))
    )
    (net (code "58") (name "/OUT1") (class "Default")
      (node (ref "IC3") (pin "7") (pinfunction "OUT_7") (pintype "output"))
      (node (ref "R44") (pin "1") (pinfunction "1_1") (pintype "passive"))
      (node (ref "R59") (pin "1") (pinfunction "1_1") (pintype "passive"))
      (node (ref "R60") (pin "1") (pinfunction "1_1") (pintype "passive"))
    )
    (net (code "59") (name "/OUT2") (class "Default")
      (node (ref "IC3") (pin "1") (pinfunction "OUT_1") (pintype "output"))
      (node (ref "R41") (pin "1") (pinfunction "1_1") (pintype "passive"))
      (node (ref "R53") (pin "1") (pinfunction "1_1") (pintype "passive"))
      (node (ref "R54") (pin "1") (pinfunction "1_1") (pintype "passive"))
    )
    (net (code "60") (name "/OUT3") (class "Default")
      (node (ref "IC7") (pin "7") (pinfunction "OUT_7") (pintype "output"))
      (node (ref "R43") (pin "1") (pinfunction "1_1") (pintype "passive"))
      (node (ref "R57") (pin "1") (pinfunction "1_1") (pintype "passive"))
      (node (ref "R58") (pin "1") (pinfunction "1_1") (pintype "passive"))
    )
    (net (code "61") (name "/OUT4") (class "Default")
      (node (ref "IC7") (pin "8") (pinfunction "OUT_8") (pintype "output"))
      (node (ref "R42") (pin "1") (pinfunction "1_1") (pintype "passive"))
      (node (ref "R55") (pin "1") (pinfunction "1_1") (pintype "passive"))
      (node (ref "R56") (pin "1") (pinfunction "1_1") (pintype "passive"))
    )
    (net (code "62") (name "/OUT5") (class "Default")
      (node (ref "IC2") (pin "1") (pinfunction "OUT_1") (pintype "output"))
      (node (ref "R48") (pin "1") (pinfunction "1_1") (pintype "passive"))
      (node (ref "R67") (pin "1") (pinfunction "1_1") (pintype "passive"))
      (node (ref "R68") (pin "1") (pinfunction "1_1") (pintype "passive"))
    )
    (net (code "63") (name "/OUT6") (class "Default")
      (node (ref "IC2") (pin "14") (pinfunction "OUT_14") (pintype "output"))
      (node (ref "R45") (pin "1") (pinfunction "1_1") (pintype "passive"))
      (node (ref "R61") (pin "1") (pinfunction "1_1") (pintype "passive"))
      (node (ref "R62") (pin "1") (pinfunction "1_1") (pintype "passive"))
    )
    (net (code "64") (name "/OUT7") (class "Default")
      (node (ref "IC6") (pin "6") (pinfunction "-IN_6") (pintype "input"))
      (node (ref "IC6") (pin "7") (pinfunction "OUT_7") (pintype "output"))
      (node (ref "R65") (pin "1") (pinfunction "1_1") (pintype "passive"))
      (node (ref "R66") (pin "1") (pinfunction "1_1") (pintype "passive"))
    )
    (net (code "65") (name "/OUT8") (class "Default")
      (node (ref "IC6") (pin "1") (pinfunction "OUT_1") (pintype "output"))
      (node (ref "IC6") (pin "2") (pinfunction "-IN_2") (pintype "input"))
      (node (ref "R63") (pin "1") (pinfunction "1_1") (pintype "passive"))
      (node (ref "R64") (pin "1") (pinfunction "1_1") (pintype "passive"))
    )
    (net (code "66") (name "/OUT_A") (class "Default")
      (node (ref "IC2") (pin "7") (pinfunction "OUT_7") (pintype "output"))
      (node (ref "R52") (pin "1") (pinfunction "1_1") (pintype "passive"))
      (node (ref "U$2") (pin "2") (pinfunction "2_2") (pintype "passive"))
    )
    (net (code "67") (name "/OUT_B") (class "Default")
      (node (ref "IC2") (pin "8") (pinfunction "OUT_8") (pintype "output"))
      (node (ref "R50") (pin "1") (pinfunction "1_1") (pintype "passive"))
      (node (ref "U$2") (pin "3") (pinfunction "3_3") (pintype "passive"))
    )
    (net (code "68") (name "/SCL") (class "Default")
      (node (ref "IC1") (pin "22") (pinfunction "SCL_22") (pintype "bidirectional"))
      (node (ref "U$3") (pin "3") (pinfunction "3_3") (pintype "passive"))
    )
    (net (code "69") (name "/SDA") (class "Default")
      (node (ref "IC1") (pin "23") (pinfunction "SDA_23") (pintype "bidirectional"))
      (node (ref "U$3") (pin "2") (pinfunction "2_2") (pintype "passive"))
    )
    (net (code "70") (name "/SUM1") (class "Default")
      (node (ref "DA2") (pin "15") (pinfunction "IN4_15") (pintype "input"))
      (node (ref "R13") (pin "2") (pinfunction "2_2") (pintype "passive"))
    )
    (net (code "71") (name "/SUM2") (class "Default")
      (node (ref "DA2") (pin "2") (pinfunction "IN1_2") (pintype "input"))
      (node (ref "R4") (pin "2") (pinfunction "2_2") (pintype "passive"))
    )
    (net (code "72") (name "/SUM3") (class "Default")
      (node (ref "DA2") (pin "10") (pinfunction "IN3_10") (pintype "input"))
      (node (ref "R10") (pin "2") (pinfunction "2_2") (pintype "passive"))
    )
    (net (code "73") (name "/SUM4") (class "Default")
      (node (ref "DA2") (pin "7") (pinfunction "IN2_7") (pintype "input"))
      (node (ref "R7") (pin "2") (pinfunction "2_2") (pintype "passive"))
    )
    (net (code "74") (name "/SUM5") (class "Default")
      (node (ref "DA3") (pin "15") (pinfunction "IN4_15") (pintype "input"))
      (node (ref "R25") (pin "2") (pinfunction "2_2") (pintype "passive"))
    )
    (net (code "75") (name "/SUM6") (class "Default")
      (node (ref "DA3") (pin "2") (pinfunction "IN1_2") (pintype "input"))
      (node (ref "R16") (pin "2") (pinfunction "2_2") (pintype "passive"))
      (node (ref "R70") (pin "2") (pinfunction "2_2") (pintype "passive"))
    )
    (net (code "76") (name "/SUM7") (class "Default")
      (node (ref "DA3") (pin "10") (pinfunction "IN3_10") (pintype "input"))
      (node (ref "R22") (pin "2") (pinfunction "2_2") (pintype "passive"))
    )
    (net (code "77") (name "/SUM8") (class "Default")
      (node (ref "DA3") (pin "7") (pinfunction "IN2_7") (pintype "input"))
      (node (ref "R19") (pin "2") (pinfunction "2_2") (pintype "passive"))
    )
    (net (code "78") (name "/SUM_A") (class "Default")
      (node (ref "C24") (pin "2") (pinfunction "2_2") (pintype "passive"))
      (node (ref "IC4") (pin "1") (pinfunction "OUT_1") (pintype "output"))
      (node (ref "R37") (pin "1") (pinfunction "1_1") (pintype "passive"))
      (node (ref "R79") (pin "2") (pinfunction "2_2") (pintype "passive"))
      (node (ref "U$3") (pin "13") (pinfunction "13_13") (pintype "passive"))
    )
    (net (code "79") (name "/SUM_B") (class "Default")
      (node (ref "C25") (pin "2") (pinfunction "2_2") (pintype "passive"))
      (node (ref "IC4") (pin "14") (pinfunction "OUT_14") (pintype "output"))
      (node (ref "R28") (pin "1") (pinfunction "1_1") (pintype "passive"))
      (node (ref "R80") (pin "2") (pinfunction "2_2") (pintype "passive"))
      (node (ref "U$3") (pin "14") (pinfunction "14_14") (pintype "passive"))
    )
    (net (code "80") (name "/SUM_FX_A") (class "Default")
      (node (ref "C26") (pin "2") (pinfunction "2_2") (pintype "passive"))
      (node (ref "IC4") (pin "7") (pinfunction "OUT_7") (pintype "output"))
      (node (ref "R34") (pin "1") (pinfunction "1_1") (pintype "passive"))
      (node (ref "R81") (pin "2") (pinfunction "2_2") (pintype "passive"))
    )
    (net (code "81") (name "/SUM_FX_B") (class "Default")
      (node (ref "C27") (pin "2") (pinfunction "2_2") (pintype "passive"))
      (node (ref "IC4") (pin "8") (pinfunction "OUT_8") (pintype "output"))
      (node (ref "R31") (pin "1") (pinfunction "1_1") (pintype "passive"))
      (node (ref "R82") (pin "2") (pinfunction "2_2") (pintype "passive"))
    )
    (net (code "82") (name "/SVF_CHAIN") (class "Default")
      (node (ref "JP1") (pin "1") (pinfunction "1_1") (pintype "passive"))
      (node (ref "R99") (pin "2") (pinfunction "2_2") (pintype "passive"))
      (node (ref "U$3") (pin "16") (pinfunction "16_16") (pintype "passive"))
    )
    (net (code "83") (name "/SVF_CHAIN_SELECTED") (class "Default")
      (node (ref "JP1") (pin "2") (pinfunction "2_2") (pintype "passive"))
      (node (ref "JP4") (pin "2") (pinfunction "2_2") (pintype "passive"))
      (node (ref "R69") (pin "2") (pinfunction "2_2") (pintype "passive"))
    )
    (net (code "84") (name "/SW1A") (class "Default")
      (node (ref "IC8") (pin "2") (pinfunction "D_2") (pintype "bidirectional"))
      (node (ref "R59") (pin "2") (pinfunction "2_2") (pintype "passive"))
    )
    (net (code "85") (name "/SW1B") (class "Default")
      (node (ref "IC8") (pin "15") (pinfunction "D_15") (pintype "bidirectional"))
      (node (ref "R60") (pin "2") (pinfunction "2_2") (pintype "passive"))
    )
    (net (code "86") (name "/SW2A") (class "Default")
      (node (ref "IC8") (pin "7") (pinfunction "D_7") (pintype "bidirectional"))
      (node (ref "R53") (pin "2") (pinfunction "2_2") (pintype "passive"))
    )
    (net (code "87") (name "/SW2B") (class "Default")
      (node (ref "IC8") (pin "10") (pinfunction "D_10") (pintype "bidirectional"))
      (node (ref "R54") (pin "2") (pinfunction "2_2") (pintype "passive"))
    )
    (net (code "88") (name "/SW3A") (class "Default")
      (node (ref "IC9") (pin "2") (pinfunction "D_2") (pintype "bidirectional"))
      (node (ref "R57") (pin "2") (pinfunction "2_2") (pintype "passive"))
    )
    (net (code "89") (name "/SW3B") (class "Default")
      (node (ref "IC9") (pin "15") (pinfunction "D_15") (pintype "bidirectional"))
      (node (ref "R58") (pin "2") (pinfunction "2_2") (pintype "passive"))
    )
    (net (code "90") (name "/SW4A") (class "Default")
      (node (ref "IC9") (pin "7") (pinfunction "D_7") (pintype "bidirectional"))
      (node (ref "R55") (pin "2") (pinfunction "2_2") (pintype "passive"))
    )
    (net (code "91") (name "/SW4B") (class "Default")
      (node (ref "IC9") (pin "10") (pinfunction "D_10") (pintype "bidirectional"))
      (node (ref "R56") (pin "2") (pinfunction "2_2") (pintype "passive"))
    )
    (net (code "92") (name "/SW5A") (class "Default")
      (node (ref "IC10") (pin "2") (pinfunction "D_2") (pintype "bidirectional"))
      (node (ref "R67") (pin "2") (pinfunction "2_2") (pintype "passive"))
    )
    (net (code "93") (name "/SW5B") (class "Default")
      (node (ref "IC10") (pin "15") (pinfunction "D_15") (pintype "bidirectional"))
      (node (ref "R68") (pin "2") (pinfunction "2_2") (pintype "passive"))
    )
    (net (code "94") (name "/SW6A") (class "Default")
      (node (ref "IC10") (pin "7") (pinfunction "D_7") (pintype "bidirectional"))
      (node (ref "R61") (pin "2") (pinfunction "2_2") (pintype "passive"))
    )
    (net (code "95") (name "/SW6B") (class "Default")
      (node (ref "IC10") (pin "10") (pinfunction "D_10") (pintype "bidirectional"))
      (node (ref "R62") (pin "2") (pinfunction "2_2") (pintype "passive"))
    )
    (net (code "96") (name "/SW7A") (class "Default")
      (node (ref "IC11") (pin "2") (pinfunction "D_2") (pintype "bidirectional"))
      (node (ref "R65") (pin "2") (pinfunction "2_2") (pintype "passive"))
    )
    (net (code "97") (name "/SW7B") (class "Default")
      (node (ref "IC11") (pin "15") (pinfunction "D_15") (pintype "bidirectional"))
      (node (ref "R66") (pin "2") (pinfunction "2_2") (pintype "passive"))
    )
    (net (code "98") (name "/SW8A") (class "Default")
      (node (ref "IC11") (pin "7") (pinfunction "D_7") (pintype "bidirectional"))
      (node (ref "R63") (pin "2") (pinfunction "2_2") (pintype "passive"))
    )
    (net (code "99") (name "/SW8B") (class "Default")
      (node (ref "IC11") (pin "10") (pinfunction "D_10") (pintype "bidirectional"))
      (node (ref "R64") (pin "2") (pinfunction "2_2") (pintype "passive"))
    )
    (net (code "100") (name "/VL") (class "Default")
      (node (ref "IC10") (pin "12") (pinfunction "VL_12") (pintype "bidirectional"))
      (node (ref "IC11") (pin "12") (pinfunction "VL_12") (pintype "bidirectional"))
      (node (ref "IC8") (pin "12") (pinfunction "VL_12") (pintype "bidirectional"))
      (node (ref "IC9") (pin "12") (pinfunction "VL_12") (pintype "bidirectional"))
      (node (ref "R77") (pin "2") (pinfunction "2_2") (pintype "passive"))
      (node (ref "R78") (pin "1") (pinfunction "1_1") (pintype "passive"))
    )
    (net (code "101") (name "/~{RST}") (class "Default")
      (node (ref "IC1") (pin "3") (pinfunction "~{RESET}_3") (pintype "bidirectional"))
      (node (ref "R1") (pin "2") (pinfunction "2_2") (pintype "passive"))
    )
    (net (code "102") (name "GND") (class "Default")
      (node (ref "C1") (pin "1") (pinfunction "1_1") (pintype "passive"))
      (node (ref "C10") (pin "2") (pinfunction "2_2") (pintype "passive"))
      (node (ref "C11") (pin "1") (pinfunction "1_1") (pintype "passive"))
      (node (ref "C12") (pin "2") (pinfunction "2_2") (pintype "passive"))
      (node (ref "C13") (pin "1") (pinfunction "1_1") (pintype "passive"))
      (node (ref "C14") (pin "1") (pinfunction "1_1") (pintype "passive"))
      (node (ref "C15") (pin "1") (pinfunction "1_1") (pintype "passive"))
      (node (ref "C16") (pin "1") (pinfunction "1_1") (pintype "passive"))
      (node (ref "C17") (pin "2") (pinfunction "2_2") (pintype "passive"))
      (node (ref "C18") (pin "2") (pinfunction "2_2") (pintype "passive"))
      (node (ref "C19") (pin "1") (pinfunction "1_1") (pintype "passive"))
      (node (ref "C2") (pin "2") (pinfunction "2_2") (pintype "passive"))
      (node (ref "C20") (pin "2") (pinfunction "2_2") (pintype "passive"))
      (node (ref "C21") (pin "1") (pinfunction "1_1") (pintype "passive"))
      (node (ref "C22") (pin "2") (pinfunction "2_2") (pintype "passive"))
      (node (ref "C23") (pin "1") (pinfunction "1_1") (pintype "passive"))
      (node (ref "C28") (pin "1") (pinfunction "1_1") (pintype "passive"))
      (node (ref "C29") (pin "2") (pinfunction "2_2") (pintype "passive"))
      (node (ref "C3") (pin "1") (pinfunction "1_1") (pintype "passive"))
      (node (ref "C30") (pin "1") (pinfunction "1_1") (pintype "passive"))
      (node (ref "C31") (pin "2") (pinfunction "2_2") (pintype "passive"))
      (node (ref "C32") (pin "1") (pinfunction "1_1") (pintype "passive"))
      (node (ref "C4") (pin "2") (pinfunction "2_2") (pintype "passive"))
      (node (ref "C5") (pin "1") (pinfunction "1_1") (pintype "passive"))
      (node (ref "C6") (pin "2") (pinfunction "2_2") (pintype "passive"))
      (node (ref "C7") (pin "1") (pinfunction "1_1") (pintype "passive"))
      (node (ref "C8") (pin "2") (pinfunction "2_2") (pintype "passive"))
      (node (ref "C9") (pin "1") (pinfunction "1_1") (pintype "passive"))
      (node (ref "DA1") (pin "8") (pinfunction "GND_8") (pintype "power_in"))
      (node (ref "DA2") (pin "8") (pinfunction "GND_8") (pintype "power_in"))
      (node (ref "DA3") (pin "8") (pinfunction "GND_8") (pintype "power_in"))
      (node (ref "IC1") (pin "12") (pinfunction "VSS_12") (pintype "power_in"))
      (node (ref "IC1") (pin "2") (pinfunction "A1_2") (pintype "bidirectional"))
      (node (ref "IC1") (pin "21") (pinfunction "A0_21") (pintype "bidirectional"))
      (node (ref "IC10") (pin "5") (pinfunction "AGND_5") (pintype "power_in"))
      (node (ref "IC11") (pin "5") (pinfunction "AGND_5") (pintype "power_in"))
      (node (ref "IC2") (pin "10") (pinfunction "+IN_10") (pintype "input"))
      (node (ref "IC2") (pin "12") (pinfunction "+IN_12") (pintype "input"))
      (node (ref "IC2") (pin "3") (pinfunction "+IN_3") (pintype "input"))
      (node (ref "IC3") (pin "3") (pinfunction "+IN_3") (pintype "input"))
      (node (ref "IC3") (pin "5") (pinfunction "+IN_5") (pintype "input"))
      (node (ref "IC4") (pin "10") (pinfunction "+IN_10") (pintype "input"))
      (node (ref "IC4") (pin "12") (pinfunction "+IN_12") (pintype "input"))
      (node (ref "IC4") (pin "3") (pinfunction "+IN_3") (pintype "input"))
      (node (ref "IC4") (pin "5") (pinfunction "+IN_5") (pintype "input"))
      (node (ref "IC7") (pin "10") (pinfunction "+IN_10") (pintype "input"))
      (node (ref "IC7") (pin "12") (pinfunction "+IN_12") (pintype "input"))
      (node (ref "IC7") (pin "3") (pinfunction "+IN_3") (pintype "input"))
      (node (ref "IC7") (pin "5") (pinfunction "+IN_5") (pintype "input"))
      (node (ref "IC8") (pin "5") (pinfunction "AGND_5") (pintype "power_in"))
      (node (ref "IC9") (pin "5") (pinfunction "AGND_5") (pintype "power_in"))
      (node (ref "R12") (pin "1") (pinfunction "1_1") (pintype "passive"))
      (node (ref "R15") (pin "1") (pinfunction "1_1") (pintype "passive"))
      (node (ref "R18") (pin "1") (pinfunction "1_1") (pintype "passive"))
      (node (ref "R21") (pin "1") (pinfunction "1_1") (pintype "passive"))
      (node (ref "R24") (pin "1") (pinfunction "1_1") (pintype "passive"))
      (node (ref "R27") (pin "1") (pinfunction "1_1") (pintype "passive"))
      (node (ref "R3") (pin "1") (pinfunction "1_1") (pintype "passive"))
      (node (ref "R30") (pin "1") (pinfunction "1_1") (pintype "passive"))
      (node (ref "R33") (pin "1") (pinfunction "1_1") (pintype "passive"))
      (node (ref "R36") (pin "1") (pinfunction "1_1") (pintype "passive"))
      (node (ref "R46") (pin "2") (pinfunction "2_2") (pintype "passive"))
      (node (ref "R47") (pin "2") (pinfunction "2_2") (pintype "passive"))
      (node (ref "R49") (pin "2") (pinfunction "2_2") (pintype "passive"))
      (node (ref "R6") (pin "1") (pinfunction "1_1") (pintype "passive"))
      (node (ref "R73") (pin "1") (pinfunction "1_1") (pintype "passive"))
      (node (ref "R74") (pin "1") (pinfunction "1_1") (pintype "passive"))
      (node (ref "R75") (pin "1") (pinfunction "1_1") (pintype "passive"))
      (node (ref "R76") (pin "1") (pinfunction "1_1") (pintype "passive"))
      (node (ref "R78") (pin "2") (pinfunction "2_2") (pintype "passive"))
      (node (ref "R9") (pin "1") (pinfunction "1_1") (pintype "passive"))
      (node (ref "U$2") (pin "7") (pinfunction "7_7") (pintype "passive"))
      (node (ref "U$3") (pin "4") (pinfunction "4_4") (pintype "passive"))
    )
    (net (code "103") (name "Net-(C13-Pad2)") (class "Default")
      (node (ref "C13") (pin "2") (pinfunction "2_2") (pintype "passive"))
      (node (ref "R38") (pin "1") (pinfunction "1_1") (pintype "passive"))
    )
    (net (code "104") (name "Net-(C14-Pad2)") (class "Default")
      (node (ref "C14") (pin "2") (pinfunction "2_2") (pintype "passive"))
      (node (ref "R39") (pin "1") (pinfunction "1_1") (pintype "passive"))
    )
    (net (code "105") (name "Net-(C15-Pad2)") (class "Default")
      (node (ref "C15") (pin "2") (pinfunction "2_2") (pintype "passive"))
      (node (ref "R40") (pin "1") (pinfunction "1_1") (pintype "passive"))
    )
    (net (code "106") (name "Net-(DA1B-CV2)") (class "Default")
      (node (ref "DA1") (pin "6") (pinfunction "CV2_6") (pintype "input"))
      (node (ref "R29") (pin "2") (pinfunction "2_2") (pintype "passive"))
      (node (ref "R30") (pin "2") (pinfunction "2_2") (pintype "passive"))
    )
    (net (code "107") (name "Net-(DA1B-CV3)") (class "Default")
      (node (ref "DA1") (pin "11") (pinfunction "CV3_11") (pintype "input"))
      (node (ref "R32") (pin "2") (pinfunction "2_2") (pintype "passive"))
      (node (ref "R33") (pin "2") (pinfunction "2_2") (pintype "passive"))
    )
    (net (code "108") (name "Net-(DA1B-CV4)") (class "Default")
      (node (ref "DA1") (pin "14") (pinfunction "CV4_14") (pintype "input"))
      (node (ref "R35") (pin "2") (pinfunction "2_2") (pintype "passive"))
      (node (ref "R36") (pin "2") (pinfunction "2_2") (pintype "passive"))
    )
    (net (code "109") (name "Net-(DA1B-OUT1)") (class "Default")
      (node (ref "DA1") (pin "4") (pinfunction "OUT1_4") (pintype "output"))
      (node (ref "IC7") (pin "13") (pinfunction "-IN_13") (pintype "input"))
      (node (ref "R51") (pin "2") (pinfunction "2_2") (pintype "passive"))
    )
    (net (code "110") (name "Net-(DA1B-OUT2)") (class "Default")
      (node (ref "DA1") (pin "5") (pinfunction "OUT2_5") (pintype "output"))
      (node (ref "IC2") (pin "9") (pinfunction "-IN_9") (pintype "input"))
      (node (ref "R50") (pin "2") (pinfunction "2_2") (pintype "passive"))
      (node (ref "R69") (pin "1") (pinfunction "1_1") (pintype "passive"))
      (node (ref "R71") (pin "1") (pinfunction "1_1") (pintype "passive"))
    )
    (net (code "111") (name "Net-(DA1B-OUT3)") (class "Default")
      (node (ref "DA1") (pin "12") (pinfunction "OUT3_12") (pintype "output"))
      (node (ref "IC2") (pin "6") (pinfunction "-IN_6") (pintype "input"))
      (node (ref "R52") (pin "2") (pinfunction "2_2") (pintype "passive"))
    )
    (net (code "112") (name "Net-(DA1B-OUT4)") (class "Default")
      (node (ref "DA1") (pin "13") (pinfunction "OUT4_13") (pintype "output"))
      (node (ref "IC2") (pin "5") (pinfunction "+IN_5") (pintype "input"))
      (node (ref "R49") (pin "1") (pinfunction "1_1") (pintype "passive"))
    )
    (net (code "113") (name "Net-(DA1B-VREF)") (class "Default")
      (node (ref "DA1") (pin "1") (pinfunction "VREF_1") (pintype "output"))
      (node (ref "R40") (pin "2") (pinfunction "2_2") (pintype "passive"))
    )
    (net (code "114") (name "Net-(DA2B-CV2)") (class "Default")
      (node (ref "DA2") (pin "6") (pinfunction "CV2_6") (pintype "input"))
      (node (ref "R5") (pin "2") (pinfunction "2_2") (pintype "passive"))
      (node (ref "R6") (pin "2") (pinfunction "2_2") (pintype "passive"))
    )
    (net (code "115") (name "Net-(DA2B-CV3)") (class "Default")
      (node (ref "DA2") (pin "11") (pinfunction "CV3_11") (pintype "input"))
      (node (ref "R8") (pin "2") (pinfunction "2_2") (pintype "passive"))
      (node (ref "R9") (pin "2") (pinfunction "2_2") (pintype "passive"))
    )
    (net (code "116") (name "Net-(DA2B-CV4)") (class "Default")
      (node (ref "DA2") (pin "14") (pinfunction "CV4_14") (pintype "input"))
      (node (ref "R11") (pin "2") (pinfunction "2_2") (pintype "passive"))
      (node (ref "R12") (pin "2") (pinfunction "2_2") (pintype "passive"))
    )
    (net (code "117") (name "Net-(DA2B-VREF)") (class "Default")
      (node (ref "DA2") (pin "1") (pinfunction "VREF_1") (pintype "output"))
      (node (ref "R38") (pin "2") (pinfunction "2_2") (pintype "passive"))
    )
    (net (code "118") (name "Net-(DA3B-CV2)") (class "Default")
      (node (ref "DA3") (pin "6") (pinfunction "CV2_6") (pintype "input"))
      (node (ref "R17") (pin "2") (pinfunction "2_2") (pintype "passive"))
      (node (ref "R18") (pin "2") (pinfunction "2_2") (pintype "passive"))
    )
    (net (code "119") (name "Net-(DA3B-CV3)") (class "Default")
      (node (ref "DA3") (pin "11") (pinfunction "CV3_11") (pintype "input"))
      (node (ref "R20") (pin "2") (pinfunction "2_2") (pintype "passive"))
      (node (ref "R21") (pin "2") (pinfunction "2_2") (pintype "passive"))
    )
    (net (code "120") (name "Net-(DA3B-CV4)") (class "Default")
      (node (ref "DA3") (pin "14") (pinfunction "CV4_14") (pintype "input"))
      (node (ref "R23") (pin "2") (pinfunction "2_2") (pintype "passive"))
      (node (ref "R24") (pin "2") (pinfunction "2_2") (pintype "passive"))
    )
    (net (code "121") (name "Net-(DA3B-OUT2)") (class "Default")
      (node (ref "DA3") (pin "5") (pinfunction "OUT2_5") (pintype "output"))
      (node (ref "IC6") (pin "3") (pinfunction "+IN_3") (pintype "input"))
      (node (ref "R46") (pin "1") (pinfunction "1_1") (pintype "passive"))
    )
    (net (code "122") (name "Net-(DA3B-VREF)") (class "Default")
      (node (ref "DA3") (pin "1") (pinfunction "VREF_1") (pintype "output"))
      (node (ref "R39") (pin "2") (pinfunction "2_2") (pintype "passive"))
    )
    (net (code "123") (name "Net-(IC1-IO0_0)") (class "Default")
      (node (ref "IC1") (pin "4") (pinfunction "IO0_0_4") (pintype "bidirectional"))
      (node (ref "R72") (pin "1") (pinfunction "1_1") (pintype "passive"))
    )
    (net (code "124") (name "Net-(IC1-IO0_1)") (class "Default")
      (node (ref "IC1") (pin "5") (pinfunction "IO0_1_5") (pintype "bidirectional"))
      (node (ref "R83") (pin "1") (pinfunction "1_1") (pintype "passive"))
    )
    (net (code "125") (name "Net-(IC1-IO0_2)") (class "Default")
      (node (ref "IC1") (pin "6") (pinfunction "IO0_2_6") (pintype "bidirectional"))
      (node (ref "R84") (pin "1") (pinfunction "1_1") (pintype "passive"))
    )
    (net (code "126") (name "Net-(IC1-IO0_3)") (class "Default")
      (node (ref "IC1") (pin "7") (pinfunction "IO0_3_7") (pintype "bidirectional"))
      (node (ref "R85") (pin "1") (pinfunction "1_1") (pintype "passive"))
    )
    (net (code "127") (name "Net-(IC1-IO0_4)") (class "Default")
      (node (ref "IC1") (pin "8") (pinfunction "IO0_4_8") (pintype "bidirectional"))
      (node (ref "R86") (pin "1") (pinfunction "1_1") (pintype "passive"))
    )
    (net (code "128") (name "Net-(IC1-IO0_5)") (class "Default")
      (node (ref "IC1") (pin "9") (pinfunction "IO0_5_9") (pintype "bidirectional"))
      (node (ref "R87") (pin "1") (pinfunction "1_1") (pintype "passive"))
    )
    (net (code "129") (name "Net-(IC1-IO0_6)") (class "Default")
      (node (ref "IC1") (pin "10") (pinfunction "IO0_6_10") (pintype "bidirectional"))
      (node (ref "R88") (pin "1") (pinfunction "1_1") (pintype "passive"))
    )
    (net (code "130") (name "Net-(IC1-IO0_7)") (class "Default")
      (node (ref "IC1") (pin "11") (pinfunction "IO0_7_11") (pintype "bidirectional"))
      (node (ref "R89") (pin "1") (pinfunction "1_1") (pintype "passive"))
    )
    (net (code "131") (name "Net-(IC1-IO1_0)") (class "Default")
      (node (ref "IC1") (pin "13") (pinfunction "IO1_0_13") (pintype "bidirectional"))
      (node (ref "R90") (pin "1") (pinfunction "1_1") (pintype "passive"))
    )
    (net (code "132") (name "Net-(IC1-IO1_1)") (class "Default")
      (node (ref "IC1") (pin "14") (pinfunction "IO1_1_14") (pintype "bidirectional"))
      (node (ref "R91") (pin "1") (pinfunction "1_1") (pintype "passive"))
    )
    (net (code "133") (name "Net-(IC1-IO1_2)") (class "Default")
      (node (ref "IC1") (pin "15") (pinfunction "IO1_2_15") (pintype "bidirectional"))
      (node (ref "R92") (pin "1") (pinfunction "1_1") (pintype "passive"))
    )
    (net (code "134") (name "Net-(IC1-IO1_3)") (class "Default")
      (node (ref "IC1") (pin "16") (pinfunction "IO1_3_16") (pintype "bidirectional"))
      (node (ref "R93") (pin "1") (pinfunction "1_1") (pintype "passive"))
    )
    (net (code "135") (name "Net-(IC1-IO1_4)") (class "Default")
      (node (ref "IC1") (pin "17") (pinfunction "IO1_4_17") (pintype "bidirectional"))
      (node (ref "R94") (pin "1") (pinfunction "1_1") (pintype "passive"))
    )
    (net (code "136") (name "Net-(IC1-IO1_5)") (class "Default")
      (node (ref "IC1") (pin "18") (pinfunction "IO1_5_18") (pintype "bidirectional"))
      (node (ref "R95") (pin "1") (pinfunction "1_1") (pintype "passive"))
    )
    (net (code "137") (name "Net-(IC1-IO1_6)") (class "Default")
      (node (ref "IC1") (pin "19") (pinfunction "IO1_6_19") (pintype "bidirectional"))
      (node (ref "R96") (pin "1") (pinfunction "1_1") (pintype "passive"))
    )
    (net (code "138") (name "Net-(IC1-IO1_7)") (class "Default")
      (node (ref "IC1") (pin "20") (pinfunction "IO1_7_20") (pintype "bidirectional"))
      (node (ref "R97") (pin "1") (pinfunction "1_1") (pintype "passive"))
    )
    (net (code "139") (name "Net-(IC7A--IN)") (class "Default")
      (node (ref "IC7") (pin "2") (pinfunction "-IN_2") (pintype "input"))
      (node (ref "R98") (pin "2") (pinfunction "2_2") (pintype "passive"))
      (node (ref "R99") (pin "1") (pinfunction "1_1") (pintype "passive"))
    )
    (net (code "140") (name "Net-(IC7A-OUT)") (class "Default")
      (node (ref "IC7") (pin "1") (pinfunction "OUT_1") (pintype "output"))
      (node (ref "JP4") (pin "1") (pinfunction "1_1") (pintype "passive"))
      (node (ref "R98") (pin "1") (pinfunction "1_1") (pintype "passive"))
    )
    (net (code "141") (name "Net-(IC7D-OUT)") (class "Default")
      (node (ref "IC7") (pin "14") (pinfunction "OUT_14") (pintype "output"))
      (node (ref "R51") (pin "1") (pinfunction "1_1") (pintype "passive"))
      (node (ref "R71") (pin "2") (pinfunction "2_2") (pintype "passive"))
    )
    (net (code "142") (name "unconnected-(IC1-~{INT}-Pad1)") (class "Default")
      (node (ref "IC1") (pin "1") (pinfunction "~{INT}_1") (pintype "bidirectional"))
    )
  )
)
